# aw_401_powersupply.net
KiCad netlist of a schematic drawn in EAGLE
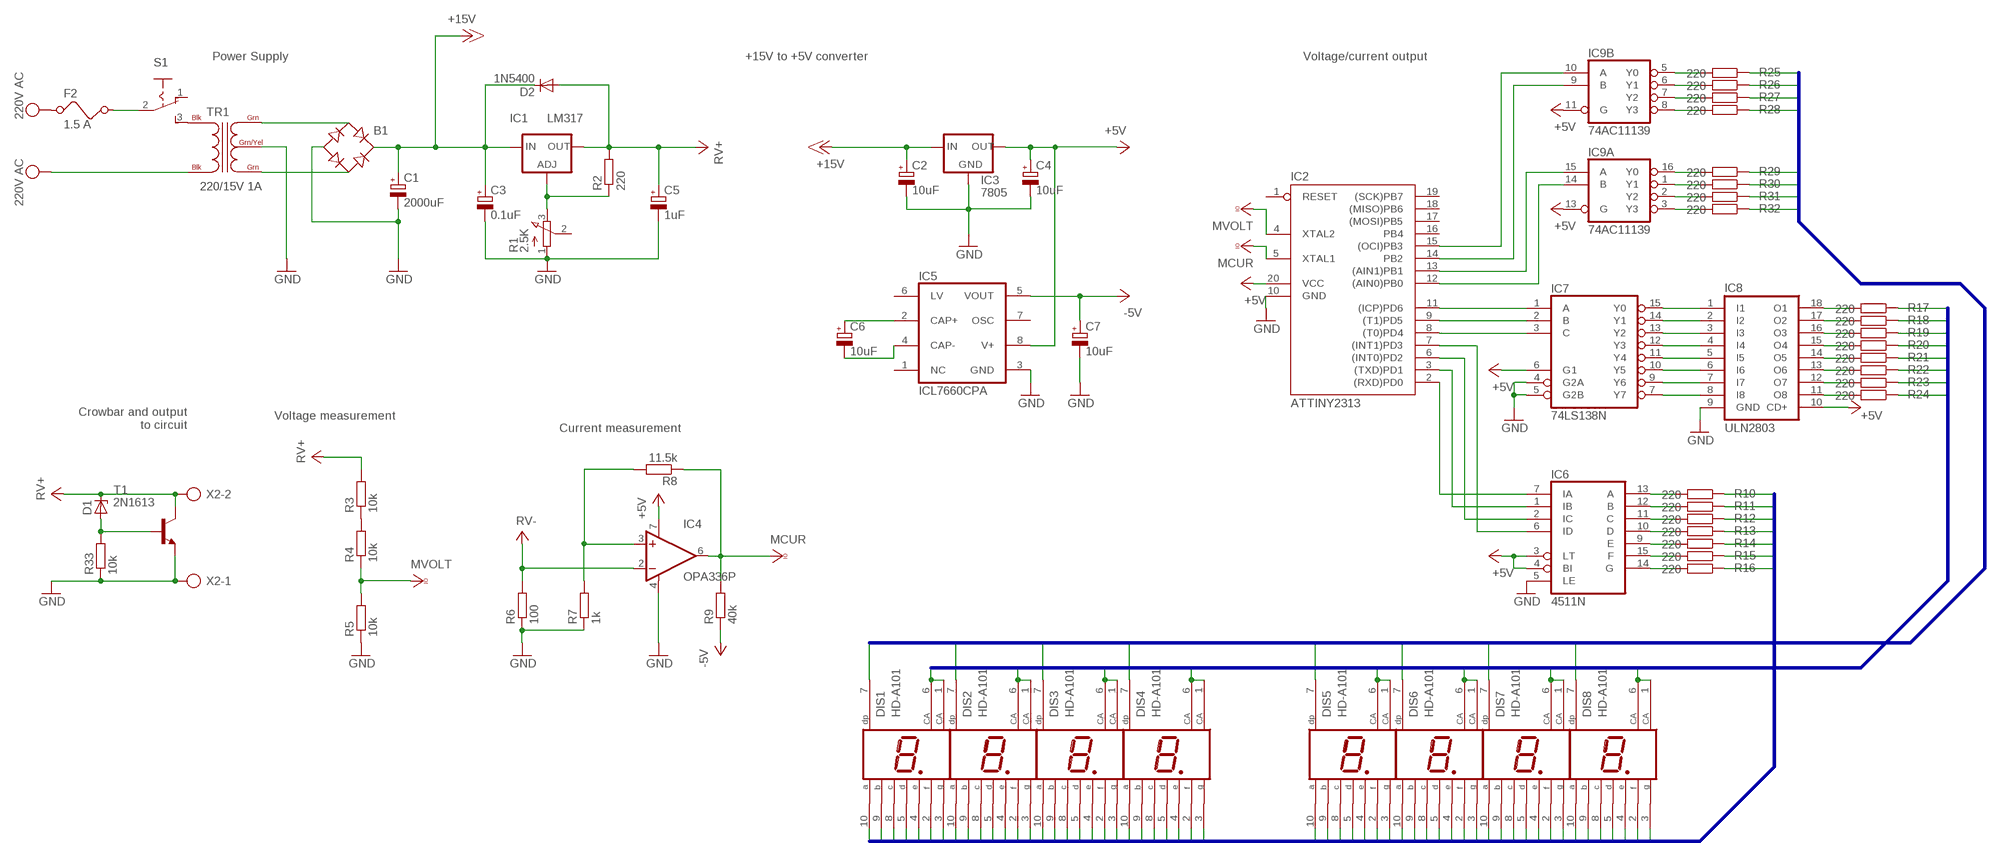
[diagram p0: schematic, sheet 1]

(export (version "E")
  (design (tool "Eeschema 10.0.6"))
  (components
    (comp (ref "B1")
      (value "RB1A")
      (footprint "eagle-import:RB1A")
      (libsource (lib "eagle-import") (part "RB1A"))
    )
    (comp (ref "C1")
      (value "2000uF")
      (footprint "eagle-import:E3,5-8")
      (libsource (lib "eagle-import") (part "CPOL-EUE3.5-8"))
    )
    (comp (ref "C2")
      (value "10uF")
      (footprint "eagle-import:E2,5-6")
      (libsource (lib "eagle-import") (part "CPOL-EUE2.5-6"))
    )
    (comp (ref "C3")
      (value "0.1uF")
      (footprint "eagle-import:E2,5-6")
      (libsource (lib "eagle-import") (part "CPOL-EUE2.5-6"))
    )
    (comp (ref "C4")
      (value "10uF")
      (footprint "eagle-import:E2,5-6")
      (libsource (lib "eagle-import") (part "CPOL-EUE2.5-6"))
    )
    (comp (ref "C5")
      (value "1uF")
      (footprint "eagle-import:E2,5-6")
      (libsource (lib "eagle-import") (part "CPOL-EUE2.5-6"))
    )
    (comp (ref "C6")
      (value "10uF")
      (footprint "eagle-import:E2,5-6")
      (libsource (lib "eagle-import") (part "CPOL-EUE2.5-6"))
    )
    (comp (ref "C7")
      (value "10uF")
      (footprint "eagle-import:E2,5-6")
      (libsource (lib "eagle-import") (part "CPOL-EUE2.5-6"))
    )
    (comp (ref "D1")
      (value "ZENER-DIODEC1702-15")
      (footprint "eagle-import:C1702-15")
      (libsource (lib "eagle-import") (part "ZENER-DIODEC1702-15"))
    )
    (comp (ref "D2")
      (value "1N5400")
      (footprint "eagle-import:DO201-15")
      (libsource (lib "eagle-import") (part "1N5400"))
    )
    (comp (ref "DIS1")
      (value "HD-A101")
      (footprint "eagle-import:HDSP-A")
      (libsource (lib "eagle-import") (part "HD-A101"))
    )
    (comp (ref "DIS2")
      (value "HD-A101")
      (footprint "eagle-import:HDSP-A")
      (libsource (lib "eagle-import") (part "HD-A101"))
    )
    (comp (ref "DIS3")
      (value "HD-A101")
      (footprint "eagle-import:HDSP-A")
      (libsource (lib "eagle-import") (part "HD-A101"))
    )
    (comp (ref "DIS4")
      (value "HD-A101")
      (footprint "eagle-import:HDSP-A")
      (libsource (lib "eagle-import") (part "HD-A101"))
    )
    (comp (ref "DIS5")
      (value "HD-A101")
      (footprint "eagle-import:HDSP-A")
      (libsource (lib "eagle-import") (part "HD-A101"))
    )
    (comp (ref "DIS6")
      (value "HD-A101")
      (footprint "eagle-import:HDSP-A")
      (libsource (lib "eagle-import") (part "HD-A101"))
    )
    (comp (ref "DIS7")
      (value "HD-A101")
      (footprint "eagle-import:HDSP-A")
      (libsource (lib "eagle-import") (part "HD-A101"))
    )
    (comp (ref "DIS8")
      (value "HD-A101")
      (footprint "eagle-import:HDSP-A")
      (libsource (lib "eagle-import") (part "HD-A101"))
    )
    (comp (ref "F2")
      (value "1.5 A")
      (footprint "eagle-import:FUSE")
      (libsource (lib "eagle-import") (part "FUSE"))
    )
    (comp (ref "IC1")
      (value "LM317")
      (footprint "eagle-import:317TS")
      (libsource (lib "eagle-import") (part "LM317TS"))
    )
    (comp (ref "IC2")
      (value "ATTINY2313")
      (footprint "eagle-import:DIL20")
      (libsource (lib "eagle-import") (part "AT90S2313P"))
    )
    (comp (ref "IC3")
      (value "7805")
      (footprint "eagle-import:78XXS")
      (libsource (lib "eagle-import") (part "78XXS"))
    )
    (comp (ref "IC4")
      (value "OPA336P")
      (footprint "eagle-import:DIL08")
      (libsource (lib "eagle-import") (part "OPA336P"))
    )
    (comp (ref "IC5")
      (value "ICL7660CPA")
      (footprint "eagle-import:DIL08")
      (fields (field (name "MF") "INTERSIL"))
      (libsource (lib "eagle-import") (part "ICL7660CPA"))
    )
    (comp (ref "IC6")
      (value "4511N")
      (footprint "eagle-import:DIL16")
      (libsource (lib "eagle-import") (part "4511N"))
    )
    (comp (ref "IC7")
      (value "74LS138N")
      (footprint "eagle-import:DIL16")
      (libsource (lib "eagle-import") (part "74138NLS"))
    )
    (comp (ref "IC8")
      (value "ULN2803")
      (footprint "eagle-import:DIL18")
      (libsource (lib "eagle-import") (part "ULN2803A"))
    )
    (comp (ref "IC9")
      (value "74AC11139")
      (footprint "eagle-import:DIL16")
      (libsource (lib "eagle-import") (part "74AC11139"))
    )
    (comp (ref "R1")
      (value "2.5K")
      (footprint "eagle-import:3RP_1610N")
      (libsource (lib "eagle-import") (part "3RP/1610N"))
    )
    (comp (ref "R2")
      (value "220")
      (footprint "eagle-import:0207_10")
      (libsource (lib "eagle-import") (part "R-EU_0207/10"))
    )
    (comp (ref "R3")
      (value "10k")
      (footprint "eagle-import:0207_10")
      (libsource (lib "eagle-import") (part "R-EU_0207/10"))
    )
    (comp (ref "R4")
      (value "10k")
      (footprint "eagle-import:0207_10")
      (libsource (lib "eagle-import") (part "R-EU_0207/10"))
    )
    (comp (ref "R5")
      (value "10k")
      (footprint "eagle-import:0207_10")
      (libsource (lib "eagle-import") (part "R-EU_0207/10"))
    )
    (comp (ref "R6")
      (value "100")
      (footprint "eagle-import:0207_10")
      (libsource (lib "eagle-import") (part "R-EU_0207/10"))
    )
    (comp (ref "R7")
      (value "1k")
      (footprint "eagle-import:0207_10")
      (libsource (lib "eagle-import") (part "R-EU_0207/10"))
    )
    (comp (ref "R8")
      (value "11.5k")
      (footprint "eagle-import:0207_10")
      (libsource (lib "eagle-import") (part "R-EU_0207/10"))
    )
    (comp (ref "R9")
      (value "40k")
      (footprint "eagle-import:0207_10")
      (libsource (lib "eagle-import") (part "R-EU_0207/10"))
    )
    (comp (ref "R10")
      (value "220")
      (footprint "eagle-import:0207_10")
      (libsource (lib "eagle-import") (part "R-EU_0207/10"))
    )
    (comp (ref "R11")
      (value "220")
      (footprint "eagle-import:0207_10")
      (libsource (lib "eagle-import") (part "R-EU_0207/10"))
    )
    (comp (ref "R12")
      (value "220")
      (footprint "eagle-import:0207_10")
      (libsource (lib "eagle-import") (part "R-EU_0207/10"))
    )
    (comp (ref "R13")
      (value "220")
      (footprint "eagle-import:0207_10")
      (libsource (lib "eagle-import") (part "R-EU_0207/10"))
    )
    (comp (ref "R14")
      (value "220")
      (footprint "eagle-import:0207_10")
      (libsource (lib "eagle-import") (part "R-EU_0207/10"))
    )
    (comp (ref "R15")
      (value "220")
      (footprint "eagle-import:0207_10")
      (libsource (lib "eagle-import") (part "R-EU_0207/10"))
    )
    (comp (ref "R16")
      (value "220")
      (footprint "eagle-import:0207_10")
      (libsource (lib "eagle-import") (part "R-EU_0207/10"))
    )
    (comp (ref "R17")
      (value "220")
      (footprint "eagle-import:0207_10")
      (libsource (lib "eagle-import") (part "R-EU_0207/10"))
    )
    (comp (ref "R18")
      (value "220")
      (footprint "eagle-import:0207_10")
      (libsource (lib "eagle-import") (part "R-EU_0207/10"))
    )
    (comp (ref "R19")
      (value "220")
      (footprint "eagle-import:0207_10")
      (libsource (lib "eagle-import") (part "R-EU_0207/10"))
    )
    (comp (ref "R20")
      (value "220")
      (footprint "eagle-import:0207_10")
      (libsource (lib "eagle-import") (part "R-EU_0207/10"))
    )
    (comp (ref "R21")
      (value "220")
      (footprint "eagle-import:0207_10")
      (libsource (lib "eagle-import") (part "R-EU_0207/10"))
    )
    (comp (ref "R22")
      (value "220")
      (footprint "eagle-import:0207_10")
      (libsource (lib "eagle-import") (part "R-EU_0207/10"))
    )
    (comp (ref "R23")
      (value "220")
      (footprint "eagle-import:0207_10")
      (libsource (lib "eagle-import") (part "R-EU_0207/10"))
    )
    (comp (ref "R24")
      (value "220")
      (footprint "eagle-import:0207_10")
      (libsource (lib "eagle-import") (part "R-EU_0207/10"))
    )
    (comp (ref "R25")
      (value "220")
      (footprint "eagle-import:0207_10")
      (libsource (lib "eagle-import") (part "R-EU_0207/10"))
    )
    (comp (ref "R26")
      (value "220")
      (footprint "eagle-import:0207_10")
      (libsource (lib "eagle-import") (part "R-EU_0207/10"))
    )
    (comp (ref "R27")
      (value "220")
      (footprint "eagle-import:0207_10")
      (libsource (lib "eagle-import") (part "R-EU_0207/10"))
    )
    (comp (ref "R28")
      (value "220")
      (footprint "eagle-import:0207_10")
      (libsource (lib "eagle-import") (part "R-EU_0207/10"))
    )
    (comp (ref "R29")
      (value "220")
      (footprint "eagle-import:0207_10")
      (libsource (lib "eagle-import") (part "R-EU_0207/10"))
    )
    (comp (ref "R30")
      (value "220")
      (footprint "eagle-import:0207_10")
      (libsource (lib "eagle-import") (part "R-EU_0207/10"))
    )
    (comp (ref "R31")
      (value "220")
      (footprint "eagle-import:0207_10")
      (libsource (lib "eagle-import") (part "R-EU_0207/10"))
    )
    (comp (ref "R32")
      (value "220")
      (footprint "eagle-import:0207_10")
      (libsource (lib "eagle-import") (part "R-EU_0207/10"))
    )
    (comp (ref "R33")
      (value "10k")
      (footprint "eagle-import:0207_10")
      (libsource (lib "eagle-import") (part "R-EU_0207/10"))
    )
    (comp (ref "S1")
      (value "255SB")
      (footprint "eagle-import:255SB")
      (libsource (lib "eagle-import") (part "255SB"))
    )
    (comp (ref "T1")
      (value "2N1613")
      (footprint "eagle-import:TO5")
      (libsource (lib "eagle-import") (part "2N1613"))
    )
    (comp (ref "TR1")
      (value "220/15V 1A")
      (footprint "eagle-import:C2H")
      (libsource (lib "eagle-import") (part "166A24"))
    )
    (comp (ref "X2")
      (value "AK500/2")
      (footprint "eagle-import:AK500_2")
      (libsource (lib "eagle-import") (part "AK500/2"))
    )
  )
  (nets
    (net (code "1") (name "+5V") (class "Default")
      (node (ref "C4") (pin "+") (pinfunction "+_+") (pintype "passive"))
      (node (ref "IC2") (pin "20") (pinfunction "VCC_20") (pintype "power_in"))
      (node (ref "IC3") (pin "OUT") (pinfunction "OUT_OUT") (pintype "passive"))
      (node (ref "IC4") (pin "7") (pinfunction "V+_7") (pintype "power_in"))
      (node (ref "IC5") (pin "8") (pinfunction "V+_8") (pintype "power_in"))
      (node (ref "IC6") (pin "3") (pinfunction "LT_3") (pintype "input"))
      (node (ref "IC6") (pin "4") (pinfunction "BI_4") (pintype "input"))
      (node (ref "IC7") (pin "6") (pinfunction "G1_6") (pintype "input"))
      (node (ref "IC8") (pin "10") (pinfunction "CD+_10") (pintype "passive"))
      (node (ref "IC9") (pin "11") (pinfunction "G_11") (pintype "input"))
      (node (ref "IC9") (pin "13") (pinfunction "G_13") (pintype "input"))
    )
    (net (code "2") (name "+15V") (class "Default")
      (node (ref "B1") (pin "+") (pinfunction "+_+") (pintype "passive"))
      (node (ref "C1") (pin "+") (pinfunction "+_+") (pintype "passive"))
      (node (ref "C2") (pin "+") (pinfunction "+_+") (pintype "passive"))
      (node (ref "C3") (pin "+") (pinfunction "+_+") (pintype "passive"))
      (node (ref "D2") (pin "C") (pinfunction "C_C") (pintype "passive"))
      (node (ref "IC1") (pin "3") (pinfunction "IN_3") (pintype "input"))
      (node (ref "IC3") (pin "IN") (pinfunction "IN_IN") (pintype "input"))
    )
    (net (code "3") (name "-5V") (class "Default")
      (node (ref "C7") (pin "+") (pinfunction "+_+") (pintype "passive"))
      (node (ref "IC5") (pin "5") (pinfunction "VOUT_5") (pintype "output"))
      (node (ref "R9") (pin "1") (pinfunction "1_1") (pintype "passive"))
    )
    (net (code "4") (name "/ANODE1") (class "Default")
      (node (ref "DIS8") (pin "1") (pinfunction "CA_1") (pintype "passive"))
      (node (ref "DIS8") (pin "6") (pinfunction "CA_6") (pintype "passive"))
      (node (ref "R17") (pin "1") (pinfunction "1_1") (pintype "passive"))
    )
    (net (code "5") (name "/ANODE2") (class "Default")
      (node (ref "DIS7") (pin "1") (pinfunction "CA_1") (pintype "passive"))
      (node (ref "DIS7") (pin "6") (pinfunction "CA_6") (pintype "passive"))
      (node (ref "R18") (pin "1") (pinfunction "1_1") (pintype "passive"))
    )
    (net (code "6") (name "/ANODE3") (class "Default")
      (node (ref "DIS6") (pin "1") (pinfunction "CA_1") (pintype "passive"))
      (node (ref "DIS6") (pin "6") (pinfunction "CA_6") (pintype "passive"))
      (node (ref "R19") (pin "1") (pinfunction "1_1") (pintype "passive"))
    )
    (net (code "7") (name "/ANODE4") (class "Default")
      (node (ref "DIS5") (pin "1") (pinfunction "CA_1") (pintype "passive"))
      (node (ref "DIS5") (pin "6") (pinfunction "CA_6") (pintype "passive"))
      (node (ref "R20") (pin "1") (pinfunction "1_1") (pintype "passive"))
    )
    (net (code "8") (name "/ANODE5") (class "Default")
      (node (ref "DIS4") (pin "1") (pinfunction "CA_1") (pintype "passive"))
      (node (ref "DIS4") (pin "6") (pinfunction "CA_6") (pintype "passive"))
      (node (ref "R21") (pin "1") (pinfunction "1_1") (pintype "passive"))
    )
    (net (code "9") (name "/ANODE6") (class "Default")
      (node (ref "DIS3") (pin "1") (pinfunction "CA_1") (pintype "passive"))
      (node (ref "DIS3") (pin "6") (pinfunction "CA_6") (pintype "passive"))
      (node (ref "R22") (pin "1") (pinfunction "1_1") (pintype "passive"))
    )
    (net (code "10") (name "/ANODE7") (class "Default")
      (node (ref "DIS2") (pin "1") (pinfunction "CA_1") (pintype "passive"))
      (node (ref "DIS2") (pin "6") (pinfunction "CA_6") (pintype "passive"))
      (node (ref "R23") (pin "1") (pinfunction "1_1") (pintype "passive"))
    )
    (net (code "11") (name "/ANODE8") (class "Default")
      (node (ref "DIS1") (pin "1") (pinfunction "CA_1") (pintype "passive"))
      (node (ref "DIS1") (pin "6") (pinfunction "CA_6") (pintype "passive"))
      (node (ref "R24") (pin "1") (pinfunction "1_1") (pintype "passive"))
    )
    (net (code "12") (name "/DP1") (class "Default")
      (node (ref "DIS1") (pin "7") (pinfunction "DP_7") (pintype "passive"))
      (node (ref "R32") (pin "1") (pinfunction "1_1") (pintype "passive"))
    )
    (net (code "13") (name "/DP2") (class "Default")
      (node (ref "DIS2") (pin "7") (pinfunction "DP_7") (pintype "passive"))
      (node (ref "R31") (pin "1") (pinfunction "1_1") (pintype "passive"))
    )
    (net (code "14") (name "/DP3") (class "Default")
      (node (ref "DIS3") (pin "7") (pinfunction "DP_7") (pintype "passive"))
      (node (ref "R30") (pin "1") (pinfunction "1_1") (pintype "passive"))
    )
    (net (code "15") (name "/DP4") (class "Default")
      (node (ref "DIS4") (pin "7") (pinfunction "DP_7") (pintype "passive"))
      (node (ref "R29") (pin "1") (pinfunction "1_1") (pintype "passive"))
    )
    (net (code "16") (name "/DP5") (class "Default")
      (node (ref "DIS5") (pin "7") (pinfunction "DP_7") (pintype "passive"))
      (node (ref "R28") (pin "1") (pinfunction "1_1") (pintype "passive"))
    )
    (net (code "17") (name "/DP6") (class "Default")
      (node (ref "DIS6") (pin "7") (pinfunction "DP_7") (pintype "passive"))
      (node (ref "R27") (pin "1") (pinfunction "1_1") (pintype "passive"))
    )
    (net (code "18") (name "/DP7") (class "Default")
      (node (ref "DIS7") (pin "7") (pinfunction "DP_7") (pintype "passive"))
      (node (ref "R26") (pin "1") (pinfunction "1_1") (pintype "passive"))
    )
    (net (code "19") (name "/DP8") (class "Default")
      (node (ref "DIS8") (pin "7") (pinfunction "DP_7") (pintype "passive"))
      (node (ref "R25") (pin "1") (pinfunction "1_1") (pintype "passive"))
    )
    (net (code "20") (name "/PORT0") (class "Default")
      (node (ref "DIS1") (pin "10") (pinfunction "A_10") (pintype "passive"))
      (node (ref "R10") (pin "1") (pinfunction "1_1") (pintype "passive"))
    )
    (net (code "21") (name "/PORT1") (class "Default")
      (node (ref "DIS1") (pin "9") (pinfunction "B_9") (pintype "passive"))
      (node (ref "R11") (pin "1") (pinfunction "1_1") (pintype "passive"))
    )
    (net (code "22") (name "/PORT2") (class "Default")
      (node (ref "DIS1") (pin "8") (pinfunction "C_8") (pintype "passive"))
      (node (ref "R12") (pin "1") (pinfunction "1_1") (pintype "passive"))
    )
    (net (code "23") (name "/PORT3") (class "Default")
      (node (ref "DIS1") (pin "5") (pinfunction "D_5") (pintype "passive"))
      (node (ref "R13") (pin "1") (pinfunction "1_1") (pintype "passive"))
    )
    (net (code "24") (name "/PORT4") (class "Default")
      (node (ref "DIS1") (pin "4") (pinfunction "E_4") (pintype "passive"))
      (node (ref "R14") (pin "1") (pinfunction "1_1") (pintype "passive"))
    )
    (net (code "25") (name "/PORT5") (class "Default")
      (node (ref "DIS1") (pin "2") (pinfunction "F_2") (pintype "passive"))
      (node (ref "R15") (pin "1") (pinfunction "1_1") (pintype "passive"))
    )
    (net (code "26") (name "/PORT6") (class "Default")
      (node (ref "DIS1") (pin "3") (pinfunction "G_3") (pintype "passive"))
      (node (ref "R16") (pin "1") (pinfunction "1_1") (pintype "passive"))
    )
    (net (code "27") (name "220V AC") (class "Default")
      (node (ref "F2") (pin "1") (pinfunction "1_1") (pintype "passive"))
      (node (ref "TR1") (pin "BLK@2") (pinfunction "BLK_BLK@2") (pintype "passive"))
    )
    (net (code "28") (name "GND") (class "Default")
      (node (ref "B1") (pin "-") (pinfunction "-_-") (pintype "passive"))
      (node (ref "C1") (pin "-") (pinfunction "-_-") (pintype "passive"))
      (node (ref "C2") (pin "-") (pinfunction "-_-") (pintype "passive"))
      (node (ref "C3") (pin "-") (pinfunction "-_-") (pintype "passive"))
      (node (ref "C4") (pin "-") (pinfunction "-_-") (pintype "passive"))
      (node (ref "C5") (pin "-") (pinfunction "-_-") (pintype "passive"))
      (node (ref "C7") (pin "-") (pinfunction "-_-") (pintype "passive"))
      (node (ref "IC2") (pin "10") (pinfunction "GND_10") (pintype "power_in"))
      (node (ref "IC3") (pin "GND") (pinfunction "GND_GND") (pintype "input"))
      (node (ref "IC4") (pin "4") (pinfunction "V-_4") (pintype "power_in"))
      (node (ref "IC5") (pin "3") (pinfunction "GND_3") (pintype "power_in"))
      (node (ref "IC6") (pin "5") (pinfunction "LE_5") (pintype "input"))
      (node (ref "IC7") (pin "4") (pinfunction "G2A_4") (pintype "input"))
      (node (ref "IC7") (pin "5") (pinfunction "G2B_5") (pintype "input"))
      (node (ref "IC8") (pin "9") (pinfunction "GND_9") (pintype "power_in"))
      (node (ref "R1") (pin "1") (pinfunction "A_1") (pintype "passive"))
      (node (ref "R33") (pin "1") (pinfunction "1_1") (pintype "passive"))
      (node (ref "R5") (pin "1") (pinfunction "1_1") (pintype "passive"))
      (node (ref "R6") (pin "1") (pinfunction "1_1") (pintype "passive"))
      (node (ref "R7") (pin "1") (pinfunction "1_1") (pintype "passive"))
      (node (ref "T1") (pin "1") (pinfunction "E_1") (pintype "passive"))
      (node (ref "TR1") (pin "GRN/YEL") (pinfunction "GRN/YEL_GRN/YEL") (pintype "passive"))
      (node (ref "X2") (pin "1") (pinfunction "KL_1") (pintype "passive"))
    )
    (net (code "29") (name "MCUR") (class "Default")
      (node (ref "IC2") (pin "4") (pinfunction "XTAL2_4") (pintype "bidirectional"))
      (node (ref "IC2") (pin "5") (pinfunction "XTAL1_5") (pintype "bidirectional"))
      (node (ref "IC4") (pin "6") (pinfunction "OUT_6") (pintype "output"))
      (node (ref "R4") (pin "1") (pinfunction "1_1") (pintype "passive"))
      (node (ref "R5") (pin "2") (pinfunction "2_2") (pintype "passive"))
      (node (ref "R8") (pin "1") (pinfunction "1_1") (pintype "passive"))
      (node (ref "R9") (pin "2") (pinfunction "2_2") (pintype "passive"))
    )
    (net (code "30") (name "Net-(B1-PadAC1)") (class "Default")
      (node (ref "B1") (pin "AC1") (pinfunction "AC1_AC1") (pintype "passive"))
      (node (ref "TR1") (pin "GRN@1") (pinfunction "GRN_GRN@1") (pintype "passive"))
    )
    (net (code "31") (name "Net-(B1-PadAC2)") (class "Default")
      (node (ref "B1") (pin "AC2") (pinfunction "AC2_AC2") (pintype "passive"))
      (node (ref "TR1") (pin "GRN@2") (pinfunction "GRN_GRN@2") (pintype "passive"))
    )
    (net (code "32") (name "Net-(IC1-ADJ)") (class "Default")
      (node (ref "IC1") (pin "1") (pinfunction "ADJ_1") (pintype "input"))
      (node (ref "R1") (pin "3") (pinfunction "E_3") (pintype "passive"))
      (node (ref "R2") (pin "1") (pinfunction "1_1") (pintype "passive"))
    )
    (net (code "33") (name "Net-(IC2-(AIN0)PB0)") (class "Default")
      (node (ref "IC2") (pin "12") (pinfunction "(AIN0)PB0_12") (pintype "bidirectional"))
      (node (ref "IC9") (pin "14") (pinfunction "B_14") (pintype "input"))
    )
    (net (code "34") (name "Net-(IC2-(AIN1)PB1)") (class "Default")
      (node (ref "IC2") (pin "13") (pinfunction "(AIN1)PB1_13") (pintype "bidirectional"))
      (node (ref "IC9") (pin "15") (pinfunction "A_15") (pintype "input"))
    )
    (net (code "35") (name "Net-(IC2-(ICP)PD6)") (class "Default")
      (node (ref "IC2") (pin "11") (pinfunction "(ICP)PD6_11") (pintype "bidirectional"))
      (node (ref "IC7") (pin "1") (pinfunction "A_1") (pintype "input"))
    )
    (net (code "36") (name "Net-(IC2-(INT0)PD2)") (class "Default")
      (node (ref "IC2") (pin "6") (pinfunction "(INT0)PD2_6") (pintype "bidirectional"))
      (node (ref "IC6") (pin "2") (pinfunction "IC_2") (pintype "input"))
    )
    (net (code "37") (name "Net-(IC2-(INT1)PD3)") (class "Default")
      (node (ref "IC2") (pin "7") (pinfunction "(INT1)PD3_7") (pintype "bidirectional"))
      (node (ref "IC6") (pin "6") (pinfunction "ID_6") (pintype "input"))
    )
    (net (code "38") (name "Net-(IC2-(OCI)PB3)") (class "Default")
      (node (ref "IC2") (pin "15") (pinfunction "(OCI)PB3_15") (pintype "bidirectional"))
      (node (ref "IC9") (pin "10") (pinfunction "A_10") (pintype "input"))
    )
    (net (code "39") (name "Net-(IC2-(RXD)PD0)") (class "Default")
      (node (ref "IC2") (pin "2") (pinfunction "(RXD)PD0_2") (pintype "bidirectional"))
      (node (ref "IC6") (pin "7") (pinfunction "IA_7") (pintype "input"))
    )
    (net (code "40") (name "Net-(IC2-(T0)PD4)") (class "Default")
      (node (ref "IC2") (pin "8") (pinfunction "(T0)PD4_8") (pintype "bidirectional"))
      (node (ref "IC7") (pin "3") (pinfunction "C_3") (pintype "input"))
    )
    (net (code "41") (name "Net-(IC2-(T1)PD5)") (class "Default")
      (node (ref "IC2") (pin "9") (pinfunction "(T1)PD5_9") (pintype "bidirectional"))
      (node (ref "IC7") (pin "2") (pinfunction "B_2") (pintype "input"))
    )
    (net (code "42") (name "Net-(IC2-(TXD)PD1)") (class "Default")
      (node (ref "IC2") (pin "3") (pinfunction "(TXD)PD1_3") (pintype "bidirectional"))
      (node (ref "IC6") (pin "1") (pinfunction "IB_1") (pintype "input"))
    )
    (net (code "43") (name "Net-(IC2-PB2)") (class "Default")
      (node (ref "IC2") (pin "14") (pinfunction "PB2_14") (pintype "bidirectional"))
      (node (ref "IC9") (pin "9") (pinfunction "B_9") (pintype "input"))
    )
    (net (code "44") (name "Net-(IC4-+IN)") (class "Default")
      (node (ref "IC4") (pin "3") (pinfunction "+IN_3") (pintype "input"))
      (node (ref "R7") (pin "2") (pinfunction "2_2") (pintype "passive"))
      (node (ref "R8") (pin "2") (pinfunction "2_2") (pintype "passive"))
    )
    (net (code "45") (name "Net-(IC5-CAP+)") (class "Default")
      (node (ref "C6") (pin "+") (pinfunction "+_+") (pintype "passive"))
      (node (ref "IC5") (pin "2") (pinfunction "CAP+_2") (pintype "passive"))
    )
    (net (code "46") (name "Net-(IC5-CAP-)") (class "Default")
      (node (ref "C6") (pin "-") (pinfunction "-_-") (pintype "passive"))
      (node (ref "IC5") (pin "4") (pinfunction "CAP-_4") (pintype "passive"))
    )
    (net (code "47") (name "Net-(IC6A-A)") (class "Default")
      (node (ref "IC6") (pin "13") (pinfunction "A_13") (pintype "output"))
      (node (ref "R10") (pin "2") (pinfunction "2_2") (pintype "passive"))
    )
    (net (code "48") (name "Net-(IC6A-B)") (class "Default")
      (node (ref "IC6") (pin "12") (pinfunction "B_12") (pintype "output"))
      (node (ref "R11") (pin "2") (pinfunction "2_2") (pintype "passive"))
    )
    (net (code "49") (name "Net-(IC6A-C)") (class "Default")
      (node (ref "IC6") (pin "11") (pinfunction "C_11") (pintype "output"))
      (node (ref "R12") (pin "2") (pinfunction "2_2") (pintype "passive"))
    )
    (net (code "50") (name "Net-(IC6A-D)") (class "Default")
      (node (ref "IC6") (pin "10") (pinfunction "D_10") (pintype "output"))
      (node (ref "R13") (pin "2") (pinfunction "2_2") (pintype "passive"))
    )
    (net (code "51") (name "Net-(IC6A-E)") (class "Default")
      (node (ref "IC6") (pin "9") (pinfunction "E_9") (pintype "output"))
      (node (ref "R14") (pin "2") (pinfunction "2_2") (pintype "passive"))
    )
    (net (code "52") (name "Net-(IC6A-F)") (class "Default")
      (node (ref "IC6") (pin "15") (pinfunction "F_15") (pintype "output"))
      (node (ref "R15") (pin "2") (pinfunction "2_2") (pintype "passive"))
    )
    (net (code "53") (name "Net-(IC6A-G)") (class "Default")
      (node (ref "IC6") (pin "14") (pinfunction "G_14") (pintype "output"))
      (node (ref "R16") (pin "2") (pinfunction "2_2") (pintype "passive"))
    )
    (net (code "54") (name "Net-(IC7A-Y0)") (class "Default")
      (node (ref "IC7") (pin "15") (pinfunction "Y0_15") (pintype "output"))
      (node (ref "IC8") (pin "1") (pinfunction "I1_1") (pintype "input"))
    )
    (net (code "55") (name "Net-(IC7A-Y1)") (class "Default")
      (node (ref "IC7") (pin "14") (pinfunction "Y1_14") (pintype "output"))
      (node (ref "IC8") (pin "2") (pinfunction "I2_2") (pintype "input"))
    )
    (net (code "56") (name "Net-(IC7A-Y2)") (class "Default")
      (node (ref "IC7") (pin "13") (pinfunction "Y2_13") (pintype "output"))
      (node (ref "IC8") (pin "3") (pinfunction "I3_3") (pintype "input"))
    )
    (net (code "57") (name "Net-(IC7A-Y3)") (class "Default")
      (node (ref "IC7") (pin "12") (pinfunction "Y3_12") (pintype "output"))
      (node (ref "IC8") (pin "4") (pinfunction "I4_4") (pintype "input"))
    )
    (net (code "58") (name "Net-(IC7A-Y4)") (class "Default")
      (node (ref "IC7") (pin "11") (pinfunction "Y4_11") (pintype "output"))
      (node (ref "IC8") (pin "5") (pinfunction "I5_5") (pintype "input"))
    )
    (net (code "59") (name "Net-(IC7A-Y5)") (class "Default")
      (node (ref "IC7") (pin "10") (pinfunction "Y5_10") (pintype "output"))
      (node (ref "IC8") (pin "6") (pinfunction "I6_6") (pintype "input"))
    )
    (net (code "60") (name "Net-(IC7A-Y6)") (class "Default")
      (node (ref "IC7") (pin "9") (pinfunction "Y6_9") (pintype "output"))
      (node (ref "IC8") (pin "7") (pinfunction "I7_7") (pintype "input"))
    )
    (net (code "61") (name "Net-(IC7A-Y7)") (class "Default")
      (node (ref "IC7") (pin "7") (pinfunction "Y7_7") (pintype "output"))
      (node (ref "IC8") (pin "8") (pinfunction "I8_8") (pintype "input"))
    )
    (net (code "62") (name "Net-(IC8-O1)") (class "Default")
      (node (ref "IC8") (pin "18") (pinfunction "O1_18") (pintype "open_collector"))
      (node (ref "R17") (pin "2") (pinfunction "2_2") (pintype "passive"))
    )
    (net (code "63") (name "Net-(IC8-O2)") (class "Default")
      (node (ref "IC8") (pin "17") (pinfunction "O2_17") (pintype "open_collector"))
      (node (ref "R18") (pin "2") (pinfunction "2_2") (pintype "passive"))
    )
    (net (code "64") (name "Net-(IC8-O3)") (class "Default")
      (node (ref "IC8") (pin "16") (pinfunction "O3_16") (pintype "open_collector"))
      (node (ref "R19") (pin "2") (pinfunction "2_2") (pintype "passive"))
    )
    (net (code "65") (name "Net-(IC8-O4)") (class "Default")
      (node (ref "IC8") (pin "15") (pinfunction "O4_15") (pintype "open_collector"))
      (node (ref "R20") (pin "2") (pinfunction "2_2") (pintype "passive"))
    )
    (net (code "66") (name "Net-(IC8-O5)") (class "Default")
      (node (ref "IC8") (pin "14") (pinfunction "O5_14") (pintype "open_collector"))
      (node (ref "R21") (pin "2") (pinfunction "2_2") (pintype "passive"))
    )
    (net (code "67") (name "Net-(IC8-O6)") (class "Default")
      (node (ref "IC8") (pin "13") (pinfunction "O6_13") (pintype "open_collector"))
      (node (ref "R22") (pin "2") (pinfunction "2_2") (pintype "passive"))
    )
    (net (code "68") (name "Net-(IC8-O7)") (class "Default")
      (node (ref "IC8") (pin "12") (pinfunction "O7_12") (pintype "open_collector"))
      (node (ref "R23") (pin "2") (pinfunction "2_2") (pintype "passive"))
    )
    (net (code "69") (name "Net-(IC8-O8)") (class "Default")
      (node (ref "IC8") (pin "11") (pinfunction "O8_11") (pintype "open_collector"))
      (node (ref "R24") (pin "2") (pinfunction "2_2") (pintype "passive"))
    )
    (net (code "70") (name "Net-(IC9A-Y0)") (class "Default")
      (node (ref "IC9") (pin "16") (pinfunction "Y0_16") (pintype "output"))
      (node (ref "R29") (pin "2") (pinfunction "2_2") (pintype "passive"))
    )
    (net (code "71") (name "Net-(IC9A-Y1)") (class "Default")
      (node (ref "IC9") (pin "1") (pinfunction "Y1_1") (pintype "output"))
      (node (ref "R30") (pin "2") (pinfunction "2_2") (pintype "passive"))
    )
    (net (code "72") (name "Net-(IC9A-Y2)") (class "Default")
      (node (ref "IC9") (pin "2") (pinfunction "Y2_2") (pintype "output"))
      (node (ref "R31") (pin "2") (pinfunction "2_2") (pintype "passive"))
    )
    (net (code "73") (name "Net-(IC9A-Y3)") (class "Default")
      (node (ref "IC9") (pin "3") (pinfunction "Y3_3") (pintype "output"))
      (node (ref "R32") (pin "2") (pinfunction "2_2") (pintype "passive"))
    )
    (net (code "74") (name "Net-(IC9B-Y0)") (class "Default")
      (node (ref "IC9") (pin "5") (pinfunction "Y0_5") (pintype "output"))
      (node (ref "R25") (pin "2") (pinfunction "2_2") (pintype "passive"))
    )
    (net (code "75") (name "Net-(IC9B-Y1)") (class "Default")
      (node (ref "IC9") (pin "6") (pinfunction "Y1_6") (pintype "output"))
      (node (ref "R26") (pin "2") (pinfunction "2_2") (pintype "passive"))
    )
    (net (code "76") (name "Net-(IC9B-Y2)") (class "Default")
      (node (ref "IC9") (pin "7") (pinfunction "Y2_7") (pintype "output"))
      (node (ref "R27") (pin "2") (pinfunction "2_2") (pintype "passive"))
    )
    (net (code "77") (name "Net-(IC9B-Y3)") (class "Default")
      (node (ref "IC9") (pin "8") (pinfunction "Y3_8") (pintype "output"))
      (node (ref "R28") (pin "2") (pinfunction "2_2") (pintype "passive"))
    )
    (net (code "78") (name "Net-(R3-Pad1)") (class "Default")
      (node (ref "R3") (pin "1") (pinfunction "1_1") (pintype "passive"))
      (node (ref "R4") (pin "2") (pinfunction "2_2") (pintype "passive"))
    )
    (net (code "79") (name "Net-(S1-P)") (class "Default")
      (node (ref "F2") (pin "2") (pinfunction "2_2") (pintype "passive"))
      (node (ref "S1") (pin "2") (pinfunction "P_2") (pintype "passive"))
    )
    (net (code "80") (name "Net-(S1-S)") (class "Default")
      (node (ref "S1") (pin "3") (pinfunction "S_3") (pintype "passive"))
      (node (ref "TR1") (pin "BLK@1") (pinfunction "BLK_BLK@1") (pintype "passive"))
    )
    (net (code "81") (name "Net-(T1-B)") (class "Default")
      (node (ref "D1") (pin "A") (pinfunction "A_A") (pintype "passive"))
      (node (ref "R33") (pin "2") (pinfunction "2_2") (pintype "passive"))
      (node (ref "T1") (pin "2") (pinfunction "B_2") (pintype "passive"))
    )
    (net (code "82") (name "RV+") (class "Default")
      (node (ref "C5") (pin "+") (pinfunction "+_+") (pintype "passive"))
      (node (ref "D1") (pin "C") (pinfunction "C_C") (pintype "passive"))
      (node (ref "D2") (pin "A") (pinfunction "A_A") (pintype "passive"))
      (node (ref "IC1") (pin "2") (pinfunction "OUT_2") (pintype "passive"))
      (node (ref "IC4") (pin "2") (pinfunction "-IN_2") (pintype "input"))
      (node (ref "R2") (pin "2") (pinfunction "2_2") (pintype "passive"))
      (node (ref "R3") (pin "2") (pinfunction "2_2") (pintype "passive"))
      (node (ref "R6") (pin "2") (pinfunction "2_2") (pintype "passive"))
      (node (ref "T1") (pin "3") (pinfunction "C_3") (pintype "passive"))
      (node (ref "X2") (pin "2") (pinfunction "KL_2") (pintype "passive"))
    )
    (net (code "83") (name "unconnected-(DIS2-A-Pad10)") (class "Default")
      (node (ref "DIS2") (pin "10") (pinfunction "A_10") (pintype "passive"))
    )
    (net (code "84") (name "unconnected-(DIS2-B-Pad9)") (class "Default")
      (node (ref "DIS2") (pin "9") (pinfunction "B_9") (pintype "passive"))
    )
    (net (code "85") (name "unconnected-(DIS2-C-Pad8)") (class "Default")
      (node (ref "DIS2") (pin "8") (pinfunction "C_8") (pintype "passive"))
    )
    (net (code "86") (name "unconnected-(DIS2-D-Pad5)") (class "Default")
      (node (ref "DIS2") (pin "5") (pinfunction "D_5") (pintype "passive"))
    )
    (net (code "87") (name "unconnected-(DIS2-E-Pad4)") (class "Default")
      (node (ref "DIS2") (pin "4") (pinfunction "E_4") (pintype "passive"))
    )
    (net (code "88") (name "unconnected-(DIS2-F-Pad2)") (class "Default")
      (node (ref "DIS2") (pin "2") (pinfunction "F_2") (pintype "passive"))
    )
    (net (code "89") (name "unconnected-(DIS2-G-Pad3)") (class "Default")
      (node (ref "DIS2") (pin "3") (pinfunction "G_3") (pintype "passive"))
    )
    (net (code "90") (name "unconnected-(DIS3-A-Pad10)") (class "Default")
      (node (ref "DIS3") (pin "10") (pinfunction "A_10") (pintype "passive"))
    )
    (net (code "91") (name "unconnected-(DIS3-B-Pad9)") (class "Default")
      (node (ref "DIS3") (pin "9") (pinfunction "B_9") (pintype "passive"))
    )
    (net (code "92") (name "unconnected-(DIS3-C-Pad8)") (class "Default")
      (node (ref "DIS3") (pin "8") (pinfunction "C_8") (pintype "passive"))
    )
    (net (code "93") (name "unconnected-(DIS3-D-Pad5)") (class "Default")
      (node (ref "DIS3") (pin "5") (pinfunction "D_5") (pintype "passive"))
    )
    (net (code "94") (name "unconnected-(DIS3-E-Pad4)") (class "Default")
      (node (ref "DIS3") (pin "4") (pinfunction "E_4") (pintype "passive"))
    )
    (net (code "95") (name "unconnected-(DIS3-F-Pad2)") (class "Default")
      (node (ref "DIS3") (pin "2") (pinfunction "F_2") (pintype "passive"))
    )
    (net (code "96") (name "unconnected-(DIS3-G-Pad3)") (class "Default")
      (node (ref "DIS3") (pin "3") (pinfunction "G_3") (pintype "passive"))
    )
    (net (code "97") (name "unconnected-(DIS4-A-Pad10)") (class "Default")
      (node (ref "DIS4") (pin "10") (pinfunction "A_10") (pintype "passive"))
    )
    (net (code "98") (name "unconnected-(DIS4-B-Pad9)") (class "Default")
      (node (ref "DIS4") (pin "9") (pinfunction "B_9") (pintype "passive"))
    )
    (net (code "99") (name "unconnected-(DIS4-C-Pad8)") (class "Default")
      (node (ref "DIS4") (pin "8") (pinfunction "C_8") (pintype "passive"))
    )
    (net (code "100") (name "unconnected-(DIS4-D-Pad5)") (class "Default")
      (node (ref "DIS4") (pin "5") (pinfunction "D_5") (pintype "passive"))
    )
    (net (code "101") (name "unconnected-(DIS4-E-Pad4)") (class "Default")
      (node (ref "DIS4") (pin "4") (pinfunction "E_4") (pintype "passive"))
    )
    (net (code "102") (name "unconnected-(DIS4-F-Pad2)") (class "Default")
      (node (ref "DIS4") (pin "2") (pinfunction "F_2") (pintype "passive"))
    )
    (net (code "103") (name "unconnected-(DIS4-G-Pad3)") (class "Default")
      (node (ref "DIS4") (pin "3") (pinfunction "G_3") (pintype "passive"))
    )
    (net (code "104") (name "unconnected-(DIS5-A-Pad10)") (class "Default")
      (node (ref "DIS5") (pin "10") (pinfunction "A_10") (pintype "passive"))
    )
    (net (code "105") (name "unconnected-(DIS5-B-Pad9)") (class "Default")
      (node (ref "DIS5") (pin "9") (pinfunction "B_9") (pintype "passive"))
    )
    (net (code "106") (name "unconnected-(DIS5-C-Pad8)") (class "Default")
      (node (ref "DIS5") (pin "8") (pinfunction "C_8") (pintype "passive"))
    )
    (net (code "107") (name "unconnected-(DIS5-D-Pad5)") (class "Default")
      (node (ref "DIS5") (pin "5") (pinfunction "D_5") (pintype "passive"))
    )
    (net (code "108") (name "unconnected-(DIS5-E-Pad4)") (class "Default")
      (node (ref "DIS5") (pin "4") (pinfunction "E_4") (pintype "passive"))
    )
    (net (code "109") (name "unconnected-(DIS5-F-Pad2)") (class "Default")
      (node (ref "DIS5") (pin "2") (pinfunction "F_2") (pintype "passive"))
    )
    (net (code "110") (name "unconnected-(DIS5-G-Pad3)") (class "Default")
      (node (ref "DIS5") (pin "3") (pinfunction "G_3") (pintype "passive"))
    )
    (net (code "111") (name "unconnected-(DIS6-A-Pad10)") (class "Default")
      (node (ref "DIS6") (pin "10") (pinfunction "A_10") (pintype "passive"))
    )
    (net (code "112") (name "unconnected-(DIS6-B-Pad9)") (class "Default")
      (node (ref "DIS6") (pin "9") (pinfunction "B_9") (pintype "passive"))
    )
    (net (code "113") (name "unconnected-(DIS6-C-Pad8)") (class "Default")
      (node (ref "DIS6") (pin "8") (pinfunction "C_8") (pintype "passive"))
    )
    (net (code "114") (name "unconnected-(DIS6-D-Pad5)") (class "Default")
      (node (ref "DIS6") (pin "5") (pinfunction "D_5") (pintype "passive"))
    )
    (net (code "115") (name "unconnected-(DIS6-E-Pad4)") (class "Default")
      (node (ref "DIS6") (pin "4") (pinfunction "E_4") (pintype "passive"))
    )
    (net (code "116") (name "unconnected-(DIS6-F-Pad2)") (class "Default")
      (node (ref "DIS6") (pin "2") (pinfunction "F_2") (pintype "passive"))
    )
    (net (code "117") (name "unconnected-(DIS6-G-Pad3)") (class "Default")
      (node (ref "DIS6") (pin "3") (pinfunction "G_3") (pintype "passive"))
    )
    (net (code "118") (name "unconnected-(DIS7-A-Pad10)") (class "Default")
      (node (ref "DIS7") (pin "10") (pinfunction "A_10") (pintype "passive"))
    )
    (net (code "119") (name "unconnected-(DIS7-B-Pad9)") (class "Default")
      (node (ref "DIS7") (pin "9") (pinfunction "B_9") (pintype "passive"))
    )
    (net (code "120") (name "unconnected-(DIS7-C-Pad8)") (class "Default")
      (node (ref "DIS7") (pin "8") (pinfunction "C_8") (pintype "passive"))
    )
    (net (code "121") (name "unconnected-(DIS7-D-Pad5)") (class "Default")
      (node (ref "DIS7") (pin "5") (pinfunction "D_5") (pintype "passive"))
    )
    (net (code "122") (name "unconnected-(DIS7-E-Pad4)") (class "Default")
      (node (ref "DIS7") (pin "4") (pinfunction "E_4") (pintype "passive"))
    )
    (net (code "123") (name "unconnected-(DIS7-F-Pad2)") (class "Default")
      (node (ref "DIS7") (pin "2") (pinfunction "F_2") (pintype "passive"))
    )
    (net (code "124") (name "unconnected-(DIS7-G-Pad3)") (class "Default")
      (node (ref "DIS7") (pin "3") (pinfunction "G_3") (pintype "passive"))
    )
    (net (code "125") (name "unconnected-(DIS8-A-Pad10)") (class "Default")
      (node (ref "DIS8") (pin "10") (pinfunction "A_10") (pintype "passive"))
    )
    (net (code "126") (name "unconnected-(DIS8-B-Pad9)") (class "Default")
      (node (ref "DIS8") (pin "9") (pinfunction "B_9") (pintype "passive"))
    )
    (net (code "127") (name "unconnected-(DIS8-C-Pad8)") (class "Default")
      (node (ref "DIS8") (pin "8") (pinfunction "C_8") (pintype "passive"))
    )
    (net (code "128") (name "unconnected-(DIS8-D-Pad5)") (class "Default")
      (node (ref "DIS8") (pin "5") (pinfunction "D_5") (pintype "passive"))
    )
    (net (code "129") (name "unconnected-(DIS8-E-Pad4)") (class "Default")
      (node (ref "DIS8") (pin "4") (pinfunction "E_4") (pintype "passive"))
    )
    (net (code "130") (name "unconnected-(DIS8-F-Pad2)") (class "Default")
      (node (ref "DIS8") (pin "2") (pinfunction "F_2") (pintype "passive"))
    )
    (net (code "131") (name "unconnected-(DIS8-G-Pad3)") (class "Default")
      (node (ref "DIS8") (pin "3") (pinfunction "G_3") (pintype "passive"))
    )
    (net (code "132") (name "unconnected-(IC2-(MISO)PB6-Pad18)") (class "Default")
      (node (ref "IC2") (pin "18") (pinfunction "(MISO)PB6_18") (pintype "bidirectional"))
    )
    (net (code "133") (name "unconnected-(IC2-(MOSI)PB5-Pad17)") (class "Default")
      (node (ref "IC2") (pin "17") (pinfunction "(MOSI)PB5_17") (pintype "bidirectional"))
    )
    (net (code "134") (name "unconnected-(IC2-(SCK)PB7-Pad19)") (class "Default")
      (node (ref "IC2") (pin "19") (pinfunction "(SCK)PB7_19") (pintype "bidirectional"))
    )
    (net (code "135") (name "unconnected-(IC2-PB4-Pad16)") (class "Default")
      (node (ref "IC2") (pin "16") (pinfunction "PB4_16") (pintype "bidirectional"))
    )
    (net (code "136") (name "unconnected-(IC2-RESET-Pad1)") (class "Default")
      (node (ref "IC2") (pin "1") (pinfunction "RESET_1") (pintype "bidirectional"))
    )
    (net (code "137") (name "unconnected-(IC5-LV-Pad6)") (class "Default")
      (node (ref "IC5") (pin "6") (pinfunction "LV_6") (pintype "passive"))
    )
    (net (code "138") (name "unconnected-(IC5-NC-Pad1)") (class "Default")
      (node (ref "IC5") (pin "1") (pinfunction "NC_1") (pintype "no_connect"))
    )
    (net (code "139") (name "unconnected-(IC5-OSC-Pad7)") (class "Default")
      (node (ref "IC5") (pin "7") (pinfunction "OSC_7") (pintype "output"))
    )
    (net (code "140") (name "unconnected-(R1-S-Pad2)") (class "Default")
      (node (ref "R1") (pin "2") (pinfunction "S_2") (pintype "passive"))
    )
    (net (code "141") (name "unconnected-(S1-O-Pad1)") (class "Default")
      (node (ref "S1") (pin "1") (pinfunction "O_1") (pintype "passive"))
    )
  )
)
